# usb.net
KiCad netlist of a schematic drawn in EAGLE
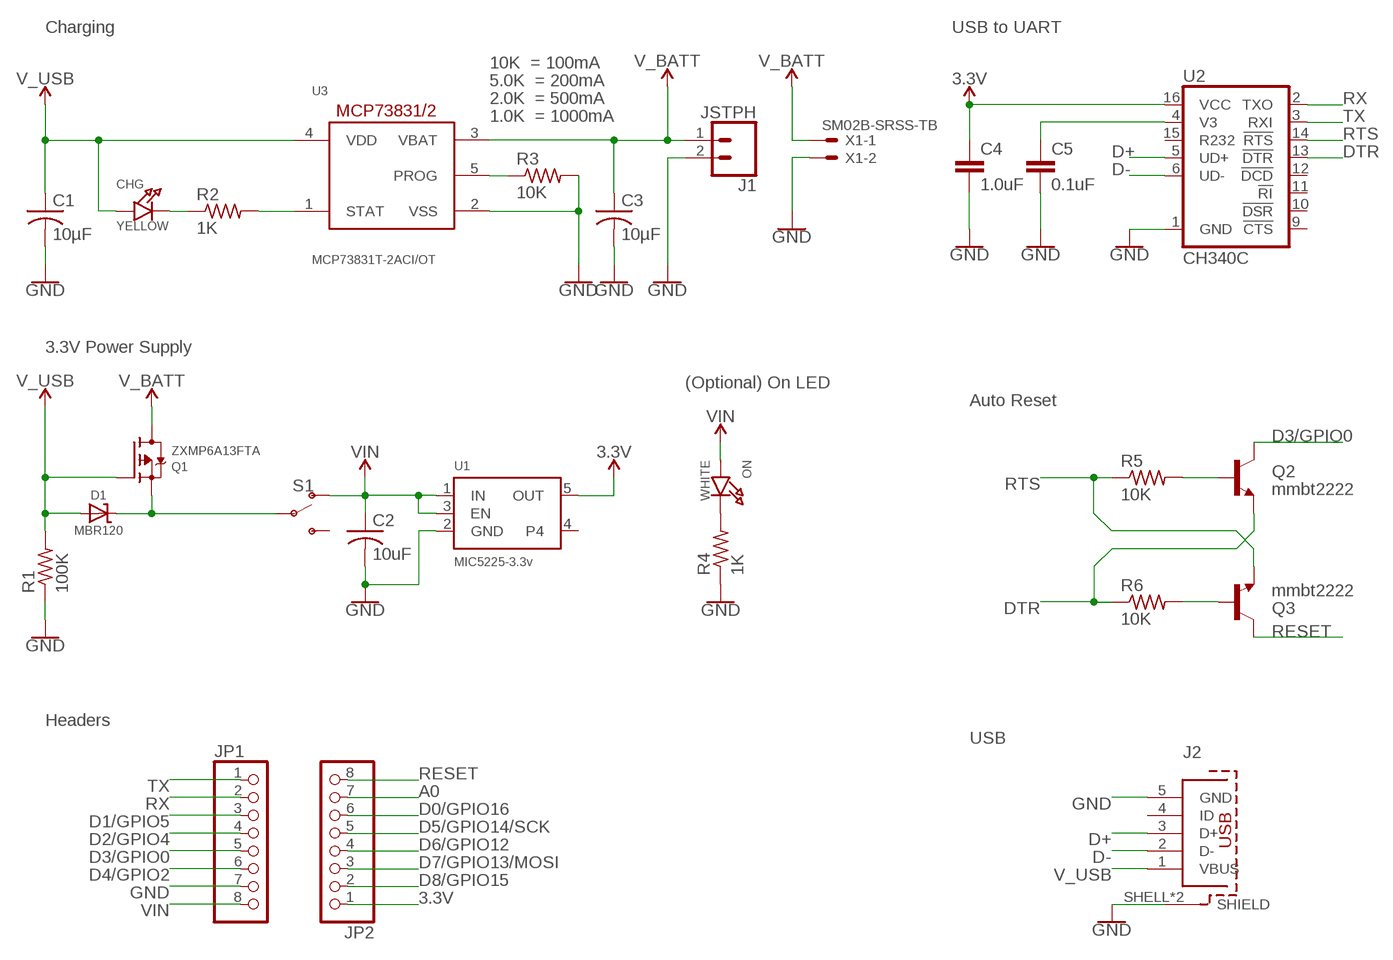
[diagram p0: schematic, sheet 1]

(export (version "E")
  (design (tool "Eeschema 10.0.6"))
  (components
    (comp (ref "C1")
      (value "10µF")
      (footprint "eagle-import:C0805")
      (fields (field (name "MPN") "CL21A106KPFNNNE"))
      (libsource (lib "eagle-import") (part "C-USC0805"))
    )
    (comp (ref "C2")
      (value "10uF")
      (footprint "eagle-import:C0805")
      (fields (field (name "MPN") "CL21A106KPFNNNE"))
      (libsource (lib "eagle-import") (part "C-USC0805"))
    )
    (comp (ref "C3")
      (value "10µF")
      (footprint "eagle-import:C0805")
      (fields (field (name "MPN") "CL21A106KPFNNNE"))
      (libsource (lib "eagle-import") (part "C-USC0805"))
    )
    (comp (ref "C4")
      (value "1.0uF")
      (footprint "eagle-import:0805")
      (fields (field (name "MPN") "C0805C105K4RAC7210"))
      (libsource (lib "eagle-import") (part "1.0UF-0805-25V-10%"))
    )
    (comp (ref "C5")
      (value "0.1uF")
      (footprint "eagle-import:0805")
      (fields (field (name "MPN") "C0805C104M3RACTU"))
      (libsource (lib "eagle-import") (part "1.0UF-0805-25V-10%"))
    )
    (comp (ref "CHG")
      (value "YELLOW")
      (footprint "eagle-import:CHIPLED_0805_NOOUTLINE")
      (fields (field (name "MPN") "NCD0805W2"))
      (libsource (lib "eagle-import") (part "LED0805_NOOUTLINE"))
    )
    (comp (ref "D1")
      (value "MBR120")
      (footprint "eagle-import:SOD-123")
      (fields (field (name "MPN") "MBR120ESFT1G"))
      (libsource (lib "eagle-import") (part "DIODE-SCHOTTKYSOD-123"))
    )
    (comp (ref "J1")
      (value "JSTPH")
      (footprint "eagle-import:1X02")
      (libsource (lib "eagle-import") (part "CONN_02"))
    )
    (comp (ref "J2")
      (value "614105150621")
      (footprint "eagle-import:614105150621")
      (fields (field (name "MPN") "U-D-M5DD-W-1"))
      (libsource (lib "eagle-import") (part "614105150621"))
    )
    (comp (ref "JP1")
      (value "PINHD-1X8CLEANBIG")
      (footprint "eagle-import:1X08-CLEANBIG")
      (fields (field (name "MPN") "C27438"))
      (libsource (lib "eagle-import") (part "PINHD-1X8CLEANBIG"))
    )
    (comp (ref "JP2")
      (value "PINHD-1X8CLEANBIG")
      (footprint "eagle-import:1X08-CLEANBIG")
      (fields (field (name "MPN") "C27438"))
      (libsource (lib "eagle-import") (part "PINHD-1X8CLEANBIG"))
    )
    (comp (ref "ON")
      (value "WHITE")
      (footprint "eagle-import:CHIPLED_0805_NOOUTLINE")
      (fields (field (name "MPN") "NCD0805W2"))
      (libsource (lib "eagle-import") (part "LED0805_NOOUTLINE"))
    )
    (comp (ref "Q1")
      (value "ZXMP6A13FTA")
      (footprint "eagle-import:SOT23-R")
      (libsource (lib "eagle-import") (part "MOSFET-P"))
    )
    (comp (ref "Q2")
      (value "mmbt2222")
      (footprint "eagle-import:SOT23-3")
      (fields (field (name "MPN") "MMBT2222A-G"))
      (libsource (lib "eagle-import") (part "TRANSISTOR_NPNSOT23-3"))
    )
    (comp (ref "Q3")
      (value "mmbt2222")
      (footprint "eagle-import:SOT23-3")
      (fields (field (name "MPN") "MMBT2222A-G"))
      (libsource (lib "eagle-import") (part "TRANSISTOR_NPNSOT23-3"))
    )
    (comp (ref "R1")
      (value "100K")
      (footprint "eagle-import:R0805")
      (fields (field (name "MPN") "0805W8F1003T5E"))
      (libsource (lib "eagle-import") (part "R-US_R0805"))
    )
    (comp (ref "R2")
      (value "1K")
      (footprint "eagle-import:R0805")
      (fields (field (name "MPN") "ESR10EZPJ102"))
      (libsource (lib "eagle-import") (part "R-US_R0805"))
    )
    (comp (ref "R3")
      (value "10K")
      (footprint "eagle-import:R0805")
      (fields (field (name "MPN") "CRCW080510K0FKEAC"))
      (libsource (lib "eagle-import") (part "R-US_R0805"))
    )
    (comp (ref "R4")
      (value "1K")
      (footprint "eagle-import:R0805")
      (fields (field (name "MPN") "ESR10EZPJ102"))
      (libsource (lib "eagle-import") (part "R-US_R0805"))
    )
    (comp (ref "R5")
      (value "10K")
      (footprint "eagle-import:R0603")
      (fields (field (name "MPN") "RC0603FR-0710KL"))
      (libsource (lib "eagle-import") (part "R-US_R0603"))
    )
    (comp (ref "R6")
      (value "10K")
      (footprint "eagle-import:R0603")
      (fields (field (name "MPN") "RC0603FR-0710KL"))
      (libsource (lib "eagle-import") (part "R-US_R0603"))
    )
    (comp (ref "S1")
      (value "SWITCH-SPDT-SMD-AYZ0202")
      (footprint "eagle-import:SWITCH_DPDT_SMD_AYZ0202")
      (fields (field (name "MPN") "AYZ0202AGRLC"))
      (libsource (lib "eagle-import") (part "SWITCH-SPDT-SMD-AYZ0202"))
    )
    (comp (ref "U1")
      (value "MIC5225-3.3v")
      (footprint "eagle-import:SOT23-5")
      (fields (field (name "MPN") "MIC5225-3.3YM5-TR"))
      (libsource (lib "eagle-import") (part "VREG_SOT23-5"))
    )
    (comp (ref "U2")
      (value "CH340C")
      (footprint "eagle-import:SO016")
      (libsource (lib "eagle-import") (part "CH340C"))
    )
    (comp (ref "U3")
      (value "MCP73831T-2ACI/OT")
      (footprint "eagle-import:SOT23-5L")
      (libsource (lib "eagle-import") (part "MCP73831/OT"))
    )
    (comp (ref "X1")
      (value "SM02B-SRSS-TB")
      (footprint "eagle-import:SM02B-SRSS-TB")
      (fields (field (name "MPN") "SM02B-SRSS-TB"))
      (libsource (lib "eagle-import") (part "?M02B-SRSS-TBS"))
    )
  )
  (nets
    (net (code "1") (name "/A0") (class "Default")
      (node (ref "JP2") (pin "7") (pinfunction "7_7") (pintype "passive"))
    )
    (net (code "2") (name "/D+") (class "Default")
      (node (ref "J2") (pin "3") (pinfunction "D+_3") (pintype "passive"))
      (node (ref "U2") (pin "5") (pinfunction "UD+_5") (pintype "bidirectional"))
    )
    (net (code "3") (name "/D-") (class "Default")
      (node (ref "J2") (pin "2") (pinfunction "D-_2") (pintype "passive"))
      (node (ref "U2") (pin "6") (pinfunction "UD-_6") (pintype "bidirectional"))
    )
    (net (code "4") (name "/D0{slash}GPIO16") (class "Default")
      (node (ref "JP2") (pin "6") (pinfunction "6_6") (pintype "passive"))
    )
    (net (code "5") (name "/D1{slash}GPIO5") (class "Default")
      (node (ref "JP1") (pin "3") (pinfunction "3_3") (pintype "passive"))
    )
    (net (code "6") (name "/D2{slash}GPIO4") (class "Default")
      (node (ref "JP1") (pin "4") (pinfunction "4_4") (pintype "passive"))
    )
    (net (code "7") (name "/D3{slash}GPIO0") (class "Default")
      (node (ref "JP1") (pin "5") (pinfunction "5_5") (pintype "passive"))
      (node (ref "Q2") (pin "3") (pinfunction "C_3") (pintype "passive"))
    )
    (net (code "8") (name "/D4{slash}GPIO2") (class "Default")
      (node (ref "JP1") (pin "6") (pinfunction "6_6") (pintype "passive"))
    )
    (net (code "9") (name "/D5{slash}GPIO14{slash}SCK") (class "Default")
      (node (ref "JP2") (pin "5") (pinfunction "5_5") (pintype "passive"))
    )
    (net (code "10") (name "/D6{slash}GPIO12") (class "Default")
      (node (ref "JP2") (pin "4") (pinfunction "4_4") (pintype "passive"))
    )
    (net (code "11") (name "/D7{slash}GPIO13{slash}MOSI") (class "Default")
      (node (ref "JP2") (pin "3") (pinfunction "3_3") (pintype "passive"))
    )
    (net (code "12") (name "/D8{slash}GPIO15") (class "Default")
      (node (ref "JP2") (pin "2") (pinfunction "2_2") (pintype "passive"))
    )
    (net (code "13") (name "/DTR") (class "Default")
      (node (ref "Q2") (pin "2") (pinfunction "E_2") (pintype "passive"))
      (node (ref "R6") (pin "1") (pinfunction "1_1") (pintype "passive"))
      (node (ref "U2") (pin "13") (pinfunction "~{DTR}_13") (pintype "bidirectional"))
    )
    (net (code "14") (name "/RESET") (class "Default")
      (node (ref "JP2") (pin "8") (pinfunction "8_8") (pintype "passive"))
      (node (ref "Q3") (pin "3") (pinfunction "C_3") (pintype "passive"))
    )
    (net (code "15") (name "/RTS") (class "Default")
      (node (ref "Q3") (pin "2") (pinfunction "E_2") (pintype "passive"))
      (node (ref "R5") (pin "1") (pinfunction "1_1") (pintype "passive"))
      (node (ref "U2") (pin "14") (pinfunction "~{RTS}_14") (pintype "bidirectional"))
    )
    (net (code "16") (name "/RX") (class "Default")
      (node (ref "JP1") (pin "2") (pinfunction "2_2") (pintype "passive"))
      (node (ref "U2") (pin "2") (pinfunction "TXO_2") (pintype "bidirectional"))
    )
    (net (code "17") (name "/TX") (class "Default")
      (node (ref "JP1") (pin "1") (pinfunction "1_1") (pintype "passive"))
      (node (ref "U2") (pin "3") (pinfunction "RXI_3") (pintype "bidirectional"))
    )
    (net (code "18") (name "3.3V") (class "Default")
      (node (ref "C4") (pin "1") (pinfunction "1_1") (pintype "passive"))
      (node (ref "JP2") (pin "1") (pinfunction "1_1") (pintype "passive"))
      (node (ref "U1") (pin "5") (pinfunction "OUT_5") (pintype "power_in"))
      (node (ref "U2") (pin "16") (pinfunction "VCC_16") (pintype "bidirectional"))
    )
    (net (code "19") (name "GND") (class "Default")
      (node (ref "C1") (pin "2") (pinfunction "2_2") (pintype "passive"))
      (node (ref "C2") (pin "2") (pinfunction "2_2") (pintype "passive"))
      (node (ref "C3") (pin "2") (pinfunction "2_2") (pintype "passive"))
      (node (ref "C4") (pin "2") (pinfunction "2_2") (pintype "passive"))
      (node (ref "C5") (pin "2") (pinfunction "2_2") (pintype "passive"))
      (node (ref "J1") (pin "2") (pinfunction "2_2") (pintype "passive"))
      (node (ref "J2") (pin "5") (pinfunction "GND_5") (pintype "passive"))
      (node (ref "J2") (pin "SHELL") (pinfunction "SHIELD_SHELL") (pintype "passive"))
      (node (ref "J2") (pin "SHELL1") (pinfunction "SHIELD_SHELL1") (pintype "passive"))
      (node (ref "JP1") (pin "7") (pinfunction "7_7") (pintype "passive"))
      (node (ref "R1") (pin "1") (pinfunction "1_1") (pintype "passive"))
      (node (ref "R3") (pin "2") (pinfunction "2_2") (pintype "passive"))
      (node (ref "R4") (pin "1") (pinfunction "1_1") (pintype "passive"))
      (node (ref "U1") (pin "2") (pinfunction "GND_2") (pintype "power_in"))
      (node (ref "U2") (pin "1") (pinfunction "GND_1") (pintype "bidirectional"))
      (node (ref "U3") (pin "2") (pinfunction "VSS_2") (pintype "power_in"))
      (node (ref "X1") (pin "2") (pinfunction "S_2") (pintype "passive"))
    )
    (net (code "20") (name "Net-(CHG-PadC)") (class "Default")
      (node (ref "CHG") (pin "C") (pinfunction "C_C") (pintype "passive"))
      (node (ref "R2") (pin "1") (pinfunction "1_1") (pintype "passive"))
    )
    (net (code "21") (name "Net-(ON-PadC)") (class "Default")
      (node (ref "ON") (pin "C") (pinfunction "C_C") (pintype "passive"))
      (node (ref "R4") (pin "2") (pinfunction "2_2") (pintype "passive"))
    )
    (net (code "22") (name "Net-(Q1-S)") (class "Default")
      (node (ref "D1") (pin "C") (pinfunction "C_C") (pintype "passive"))
      (node (ref "Q1") (pin "2") (pinfunction "S_2") (pintype "passive"))
      (node (ref "S1") (pin "5") (pinfunction "P_5") (pintype "passive"))
    )
    (net (code "23") (name "Net-(Q2-B)") (class "Default")
      (node (ref "Q2") (pin "1") (pinfunction "B_1") (pintype "passive"))
      (node (ref "R5") (pin "2") (pinfunction "2_2") (pintype "passive"))
    )
    (net (code "24") (name "Net-(Q3-B)") (class "Default")
      (node (ref "Q3") (pin "1") (pinfunction "B_1") (pintype "passive"))
      (node (ref "R6") (pin "2") (pinfunction "2_2") (pintype "passive"))
    )
    (net (code "25") (name "Net-(U2-V3)") (class "Default")
      (node (ref "C5") (pin "1") (pinfunction "1_1") (pintype "passive"))
      (node (ref "U2") (pin "4") (pinfunction "V3_4") (pintype "bidirectional"))
    )
    (net (code "26") (name "Net-(U3-PROG)") (class "Default")
      (node (ref "R3") (pin "1") (pinfunction "1_1") (pintype "passive"))
      (node (ref "U3") (pin "5") (pinfunction "PROG_5") (pintype "input"))
    )
    (net (code "27") (name "Net-(U3-STAT)") (class "Default")
      (node (ref "R2") (pin "2") (pinfunction "2_2") (pintype "passive"))
      (node (ref "U3") (pin "1") (pinfunction "STAT_1") (pintype "output"))
    )
    (net (code "28") (name "VIN") (class "Default")
      (node (ref "C2") (pin "1") (pinfunction "1_1") (pintype "passive"))
      (node (ref "JP1") (pin "8") (pinfunction "8_8") (pintype "passive"))
      (node (ref "ON") (pin "A") (pinfunction "A_A") (pintype "passive"))
      (node (ref "S1") (pin "6") (pinfunction "O_6") (pintype "passive"))
      (node (ref "U1") (pin "1") (pinfunction "IN_1") (pintype "power_in"))
      (node (ref "U1") (pin "3") (pinfunction "EN_3") (pintype "input"))
    )
    (net (code "29") (name "V_BATT") (class "Default")
      (node (ref "C3") (pin "1") (pinfunction "1_1") (pintype "passive"))
      (node (ref "J1") (pin "1") (pinfunction "1_1") (pintype "passive"))
      (node (ref "Q1") (pin "3") (pinfunction "D_3") (pintype "passive"))
      (node (ref "U3") (pin "3") (pinfunction "VBAT_3") (pintype "bidirectional"))
      (node (ref "X1") (pin "1") (pinfunction "S_1") (pintype "passive"))
    )
    (net (code "30") (name "V_USB") (class "Default")
      (node (ref "C1") (pin "1") (pinfunction "1_1") (pintype "passive"))
      (node (ref "CHG") (pin "A") (pinfunction "A_A") (pintype "passive"))
      (node (ref "D1") (pin "A") (pinfunction "A_A") (pintype "passive"))
      (node (ref "J2") (pin "1") (pinfunction "VBUS_1") (pintype "passive"))
      (node (ref "Q1") (pin "1") (pinfunction "G_1") (pintype "passive"))
      (node (ref "R1") (pin "2") (pinfunction "2_2") (pintype "passive"))
      (node (ref "U3") (pin "4") (pinfunction "VDD_4") (pintype "power_in"))
    )
    (net (code "31") (name "unconnected-(J2-ID-Pad4)") (class "Default")
      (node (ref "J2") (pin "4") (pinfunction "ID_4") (pintype "passive"))
    )
    (net (code "32") (name "unconnected-(S1-S-Pad4)") (class "Default")
      (node (ref "S1") (pin "4") (pinfunction "S_4") (pintype "passive"))
    )
    (net (code "33") (name "unconnected-(U1-P4-Pad4)") (class "Default")
      (node (ref "U1") (pin "4") (pinfunction "P4_4") (pintype "bidirectional"))
    )
    (net (code "34") (name "unconnected-(U2-R232-Pad15)") (class "Default")
      (node (ref "U2") (pin "15") (pinfunction "R232_15") (pintype "bidirectional"))
    )
    (net (code "35") (name "unconnected-(U2-~{CTS}-Pad9)") (class "Default")
      (node (ref "U2") (pin "9") (pinfunction "~{CTS}_9") (pintype "bidirectional"))
    )
    (net (code "36") (name "unconnected-(U2-~{DCD}-Pad12)") (class "Default")
      (node (ref "U2") (pin "12") (pinfunction "~{DCD}_12") (pintype "bidirectional"))
    )
    (net (code "37") (name "unconnected-(U2-~{DSR}-Pad10)") (class "Default")
      (node (ref "U2") (pin "10") (pinfunction "~{DSR}_10") (pintype "bidirectional"))
    )
    (net (code "38") (name "unconnected-(U2-~{RI}-Pad11)") (class "Default")
      (node (ref "U2") (pin "11") (pinfunction "~{RI}_11") (pintype "bidirectional"))
    )
  )
)
